# summator.net
KiCad netlist of a schematic drawn in Altium Designer
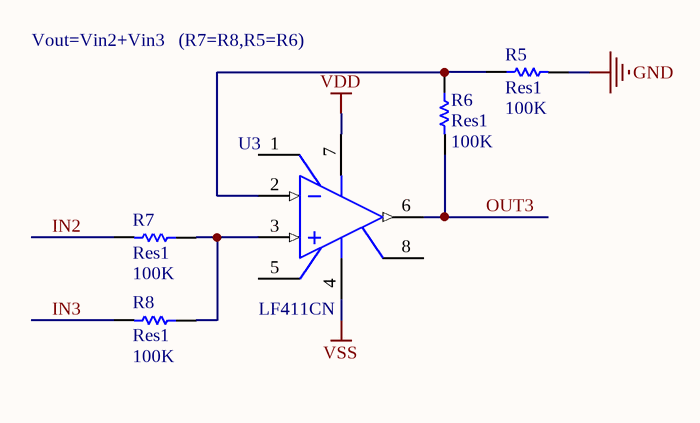
[diagram p0: summator.SchDoc]

(export (version "E")
  (design (tool "Eeschema 10.0.6"))
  (components
    (comp (ref "R5")
      (value "Res1")
      (footprint "AXIAL-0.3")
      (description "Resistor")
      (fields (field (name "ALTIUM_VALUE") "100K") (field (name "PUBLISHER") "Altium Limited"))
      (libsource (lib "Miscellaneous Devices") (part "Res1"))
    )
    (comp (ref "R6")
      (value "Res1")
      (footprint "AXIAL-0.3")
      (description "Resistor")
      (fields (field (name "ALTIUM_VALUE") "100K") (field (name "PUBLISHER") "Altium Limited"))
      (libsource (lib "Miscellaneous Devices") (part "Res1"))
    )
    (comp (ref "R7")
      (value "Res1")
      (footprint "AXIAL-0.3")
      (description "Resistor")
      (fields (field (name "ALTIUM_VALUE") "100K") (field (name "PUBLISHER") "Altium Limited"))
      (libsource (lib "Miscellaneous Devices") (part "Res1"))
    )
    (comp (ref "R8")
      (value "Res1")
      (footprint "AXIAL-0.3")
      (description "Resistor")
      (fields (field (name "ALTIUM_VALUE") "100K") (field (name "PUBLISHER") "Altium Limited"))
      (libsource (lib "Miscellaneous Devices") (part "Res1"))
    )
    (comp (ref "U3")
      (value "LF411CN")
      (footprint "N08E")
      (description "Low Offset, Low Drift JFET Input Operational Amplifier, 8-pin MDIP")
      (fields
        (field (name "MANUFACTURER") "National Semiconductor")
        (field (name "PUBLISHER") "Altium Limited")
      )
      (libsource (lib "NSC Amplifier") (part "LF411CN"))
    )
  )
  (nets
    (net (code "1") (name "/IN2") (class "Default")
      (node (ref "R7") (pin "2") (pinfunction "2_2") (pintype "passive"))
    )
    (net (code "2") (name "/IN3") (class "Default")
      (node (ref "R8") (pin "2") (pinfunction "2_2") (pintype "passive"))
    )
    (net (code "3") (name "/OUT3") (class "Default")
      (node (ref "R6") (pin "2") (pinfunction "2_2") (pintype "passive"))
      (node (ref "U3") (pin "6") (pinfunction "OUT_6") (pintype "output"))
    )
    (net (code "4") (name "GND") (class "Default")
      (node (ref "R5") (pin "2") (pinfunction "2_2") (pintype "passive"))
    )
    (net (code "5") (name "Net-(U3-IN+)") (class "Default")
      (node (ref "R7") (pin "1") (pinfunction "1_1") (pintype "passive"))
      (node (ref "R8") (pin "1") (pinfunction "1_1") (pintype "passive"))
      (node (ref "U3") (pin "3") (pinfunction "IN+_3") (pintype "input"))
    )
    (net (code "6") (name "Net-(U3-IN-)") (class "Default")
      (node (ref "R5") (pin "1") (pinfunction "1_1") (pintype "passive"))
      (node (ref "R6") (pin "1") (pinfunction "1_1") (pintype "passive"))
      (node (ref "U3") (pin "2") (pinfunction "IN-_2") (pintype "input"))
    )
    (net (code "7") (name "VDD") (class "Default")
      (node (ref "U3") (pin "7") (pinfunction "V+_7") (pintype "power_in"))
    )
    (net (code "8") (name "VSS") (class "Default")
      (node (ref "U3") (pin "4") (pinfunction "V-_4") (pintype "power_in"))
    )
    (net (code "9") (name "unconnected-(U3-BAL-Pad1)") (class "Default")
      (node (ref "U3") (pin "1") (pinfunction "BAL_1") (pintype "passive"))
    )
    (net (code "10") (name "unconnected-(U3-BAL-Pad5)") (class "Default")
      (node (ref "U3") (pin "5") (pinfunction "BAL_5") (pintype "passive"))
    )
    (net (code "11") (name "unconnected-(U3-NC-Pad8)") (class "Default")
      (node (ref "U3") (pin "8") (pinfunction "NC_8") (pintype "passive"))
    )
  )
)
